# MSXIV_BatteryModuleConnectorBoard.net
KiCad netlist of a schematic drawn in Altium Designer
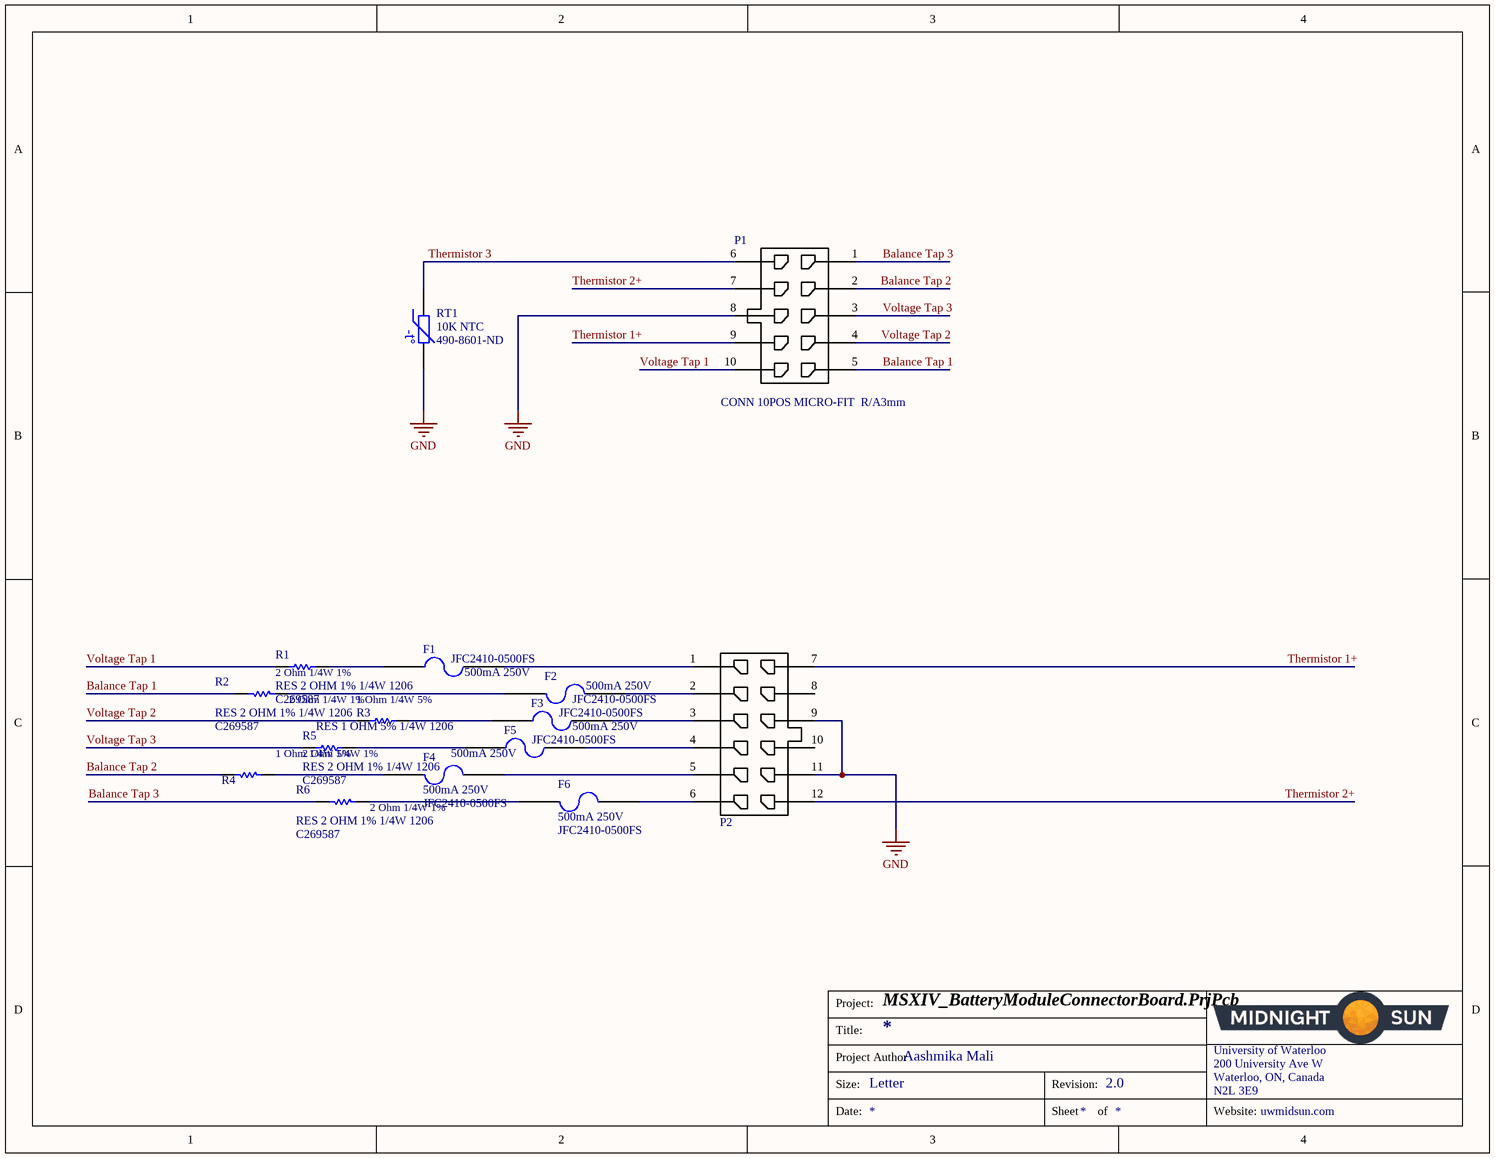
[diagram p0: MSXIV_BatteryModuleConnectorBoard.SchDoc]

(export (version "E")
  (design (tool "Eeschema 10.0.6"))
  (components
    (comp (ref "F1")
      (value "500mA 250V")
      (footprint "FUSE JFC2410-0500FS")
      (description "2410 Surface Mount Fuses RoHS")
      (fields (field (name "MANUFACTURER PART NUMBER 1") "JFC2410-0500FS"))
      (libsource (lib "") (part "FUSE 500MA LCSC_1"))
    )
    (comp (ref "F2")
      (value "500mA 250V")
      (footprint "FUSE JFC2410-0500FS")
      (description "2410 Surface Mount Fuses RoHS")
      (fields (field (name "MANUFACTURER PART NUMBER 1") "JFC2410-0500FS"))
      (libsource (lib "Schematic Diagrams") (part "FUSE 500MA LCSC"))
    )
    (comp (ref "F3")
      (value "500mA 250V")
      (footprint "FUSE JFC2410-0500FS")
      (description "2410 Surface Mount Fuses RoHS")
      (fields (field (name "MANUFACTURER PART NUMBER 1") "JFC2410-0500FS"))
      (libsource (lib "") (part "FUSE 500MA LCSC_1"))
    )
    (comp (ref "F4")
      (value "500mA 250V")
      (footprint "FUSE JFC2410-0500FS")
      (description "2410 Surface Mount Fuses RoHS")
      (fields (field (name "MANUFACTURER PART NUMBER 1") "JFC2410-0500FS"))
      (libsource (lib "Schematic Diagrams") (part "FUSE 500MA LCSC"))
    )
    (comp (ref "F5")
      (value "500mA 250V")
      (footprint "FUSE JFC2410-0500FS")
      (description "2410 Surface Mount Fuses RoHS")
      (fields (field (name "MANUFACTURER PART NUMBER 1") "JFC2410-0500FS"))
      (libsource (lib "") (part "FUSE 500MA LCSC_1"))
    )
    (comp (ref "F6")
      (value "500mA 250V")
      (footprint "FUSE JFC2410-0500FS")
      (description "2410 Surface Mount Fuses RoHS")
      (fields (field (name "MANUFACTURER PART NUMBER 1") "JFC2410-0500FS"))
      (libsource (lib "Schematic Diagrams") (part "FUSE 500MA LCSC"))
    )
    (comp (ref "P1")
      (value "CONN 10POS MICRO-FIT  R/A3mm")
      (footprint "CONN, 10POS R/A Microfit")
      (description "CONN HEADER R/A 10POS 3MM")
      (libsource (lib "Schematic Diagrams") (part "CONN 10POS MICRO-FIT  R/A3mm"))
    )
    (comp (ref "P2")
      (value "CONN 12POS HEADER R/A MICROFIT 3MM")
      (footprint "CONN, 12POS R/A Microfit")
      (description "Conn Power HDR 12 POS 3mm Solder RA Thru-Hole 12 Terminal 1 Port Micro-Fit 3.0™ Tray")
      (libsource (lib "Schematic Diagrams") (part "CONN 12POS HEADER R/A 3MM"))
    )
    (comp (ref "R1")
      (value "RES 2 OHM 1% 1/4W 1206")
      (footprint "RES 1206")
      (description "2 ±1% 1/4W 1206 Chip Resistor - Surface Mount RoHS")
      (fields (field (name "SUPPLIER PART NUMBER 1") "C269587"))
      (libsource (lib "Schematic Diagrams") (part "RES 2 OHM 1% 1/4W 1206"))
    )
    (comp (ref "R2")
      (value "RES 2 OHM 1% 1/4W 1206")
      (footprint "RES 1206")
      (description "2 ±1% 1/4W 1206 Chip Resistor - Surface Mount RoHS")
      (fields (field (name "SUPPLIER PART NUMBER 1") "C269587"))
      (libsource (lib "Schematic Diagrams") (part "RES 2 OHM 1% 1/4W 1206"))
    )
    (comp (ref "R3")
      (value "RES 1 OHM 5% 1/4W 1206")
      (footprint "RES 1206")
      (description "1 ±5% 1/4W 1206 Chip Resistor - Surface Mount RoHS")
      (libsource (lib "Schematic Diagrams") (part "RES 1 OHM 5% 1/4W 1206"))
    )
    (comp (ref "R4")
      (value "RES 1 OHM 5% 1/4W 1206")
      (footprint "RES 1206")
      (description "1 ±5% 1/4W 1206 Chip Resistor - Surface Mount RoHS")
      (libsource (lib "Schematic Diagrams") (part "RES 1 OHM 5% 1/4W 1206"))
    )
    (comp (ref "R5")
      (value "RES 2 OHM 1% 1/4W 1206")
      (footprint "RES 1206")
      (description "2 ±1% 1/4W 1206 Chip Resistor - Surface Mount RoHS")
      (fields (field (name "SUPPLIER PART NUMBER 1") "C269587"))
      (libsource (lib "Schematic Diagrams") (part "RES 2 OHM 1% 1/4W 1206"))
    )
    (comp (ref "R6")
      (value "RES 2 OHM 1% 1/4W 1206")
      (footprint "RES 1206")
      (description "2 ±1% 1/4W 1206 Chip Resistor - Surface Mount RoHS")
      (fields (field (name "SUPPLIER PART NUMBER 1") "C269587"))
      (libsource (lib "Schematic Diagrams") (part "RES 2 OHM 1% 1/4W 1206"))
    )
    (comp (ref "RT1")
      (value "10K NTC")
      (footprint "NTC THERMISTOR BEAD")
      (description "NTC Thermistor 10k Bead")
      (fields
        (field (name "MANUFACTURER") "Murata Electronics North America")
        (field (name "MANUFACTURER PART NUMBER") "NXRT15XH103FA1B030")
        (field (name "SUPPLIER PART NUMBER 1") "490-8601-ND")
      )
      (libsource (lib "Schematic Diagrams") (part "NTC THERMISTOR 10K 1% BEAD"))
    )
  )
  (nets
    (net (code "1") (name "/Balance Tap 1") (class "Default")
      (node (ref "P1") (pin "5") (pinfunction "5_5") (pintype "passive"))
      (node (ref "R2") (pin "2") (pinfunction "2_2") (pintype "passive"))
    )
    (net (code "2") (name "/Balance Tap 2") (class "Default")
      (node (ref "P1") (pin "2") (pinfunction "2_2") (pintype "passive"))
      (node (ref "R4") (pin "2") (pinfunction "2_2") (pintype "passive"))
    )
    (net (code "3") (name "/Balance Tap 3") (class "Default")
      (node (ref "P1") (pin "1") (pinfunction "1_1") (pintype "passive"))
      (node (ref "R6") (pin "2") (pinfunction "2_2") (pintype "passive"))
    )
    (net (code "4") (name "/Thermistor 1+") (class "Default")
      (node (ref "P1") (pin "9") (pinfunction "9_9") (pintype "passive"))
      (node (ref "P2") (pin "7") (pinfunction "7_7") (pintype "passive"))
    )
    (net (code "5") (name "/Thermistor 2+") (class "Default")
      (node (ref "P1") (pin "7") (pinfunction "7_7") (pintype "passive"))
      (node (ref "P2") (pin "12") (pinfunction "12_12") (pintype "passive"))
    )
    (net (code "6") (name "/Thermistor 3") (class "Default")
      (node (ref "P1") (pin "6") (pinfunction "6_6") (pintype "passive"))
      (node (ref "RT1") (pin "1") (pinfunction "1_1") (pintype "passive"))
    )
    (net (code "7") (name "/Voltage Tap 1") (class "Default")
      (node (ref "P1") (pin "10") (pinfunction "10_10") (pintype "passive"))
      (node (ref "R1") (pin "1") (pinfunction "1_1") (pintype "passive"))
    )
    (net (code "8") (name "/Voltage Tap 2") (class "Default")
      (node (ref "P1") (pin "4") (pinfunction "4_4") (pintype "passive"))
      (node (ref "R3") (pin "1") (pinfunction "1_1") (pintype "passive"))
    )
    (net (code "9") (name "/Voltage Tap 3") (class "Default")
      (node (ref "P1") (pin "3") (pinfunction "3_3") (pintype "passive"))
      (node (ref "R5") (pin "1") (pinfunction "1_1") (pintype "passive"))
    )
    (net (code "10") (name "GND") (class "Default")
      (node (ref "P1") (pin "8") (pinfunction "8_8") (pintype "passive"))
      (node (ref "P2") (pin "11") (pinfunction "11_11") (pintype "passive"))
      (node (ref "P2") (pin "9") (pinfunction "9_9") (pintype "passive"))
      (node (ref "RT1") (pin "2") (pinfunction "2_2") (pintype "passive"))
    )
    (net (code "11") (name "Net-(F1-Pad1)") (class "Default")
      (node (ref "F1") (pin "1") (pinfunction "1_1") (pintype "passive"))
      (node (ref "R1") (pin "2") (pinfunction "2_2") (pintype "passive"))
    )
    (net (code "12") (name "Net-(F1-Pad2)") (class "Default")
      (node (ref "F1") (pin "2") (pinfunction "2_2") (pintype "passive"))
      (node (ref "P2") (pin "1") (pinfunction "1_1") (pintype "passive"))
    )
    (net (code "13") (name "Net-(F2-Pad1)") (class "Default")
      (node (ref "F2") (pin "1") (pinfunction "1_1") (pintype "passive"))
      (node (ref "P2") (pin "2") (pinfunction "2_2") (pintype "passive"))
    )
    (net (code "14") (name "Net-(F2-Pad2)") (class "Default")
      (node (ref "F2") (pin "2") (pinfunction "2_2") (pintype "passive"))
      (node (ref "R2") (pin "1") (pinfunction "1_1") (pintype "passive"))
    )
    (net (code "15") (name "Net-(F3-Pad1)") (class "Default")
      (node (ref "F3") (pin "1") (pinfunction "1_1") (pintype "passive"))
      (node (ref "R3") (pin "2") (pinfunction "2_2") (pintype "passive"))
    )
    (net (code "16") (name "Net-(F3-Pad2)") (class "Default")
      (node (ref "F3") (pin "2") (pinfunction "2_2") (pintype "passive"))
      (node (ref "P2") (pin "3") (pinfunction "3_3") (pintype "passive"))
    )
    (net (code "17") (name "Net-(F4-Pad1)") (class "Default")
      (node (ref "F4") (pin "1") (pinfunction "1_1") (pintype "passive"))
      (node (ref "P2") (pin "5") (pinfunction "5_5") (pintype "passive"))
    )
    (net (code "18") (name "Net-(F4-Pad2)") (class "Default")
      (node (ref "F4") (pin "2") (pinfunction "2_2") (pintype "passive"))
      (node (ref "R4") (pin "1") (pinfunction "1_1") (pintype "passive"))
    )
    (net (code "19") (name "Net-(F5-Pad1)") (class "Default")
      (node (ref "F5") (pin "1") (pinfunction "1_1") (pintype "passive"))
      (node (ref "R5") (pin "2") (pinfunction "2_2") (pintype "passive"))
    )
    (net (code "20") (name "Net-(F5-Pad2)") (class "Default")
      (node (ref "F5") (pin "2") (pinfunction "2_2") (pintype "passive"))
      (node (ref "P2") (pin "4") (pinfunction "4_4") (pintype "passive"))
    )
    (net (code "21") (name "Net-(F6-Pad1)") (class "Default")
      (node (ref "F6") (pin "1") (pinfunction "1_1") (pintype "passive"))
      (node (ref "P2") (pin "6") (pinfunction "6_6") (pintype "passive"))
    )
    (net (code "22") (name "Net-(F6-Pad2)") (class "Default")
      (node (ref "F6") (pin "2") (pinfunction "2_2") (pintype "passive"))
      (node (ref "R6") (pin "1") (pinfunction "1_1") (pintype "passive"))
    )
    (net (code "23") (name "unconnected-(P2-Pad8)") (class "Default")
      (node (ref "P2") (pin "8") (pinfunction "8_8") (pintype "passive"))
    )
    (net (code "24") (name "unconnected-(P2-Pad10)") (class "Default")
      (node (ref "P2") (pin "10") (pinfunction "10_10") (pintype "passive"))
    )
  )
)
